# CH32L_VxxCx_Touch_Kit.net
KiCad netlist of a schematic drawn in Altium Designer
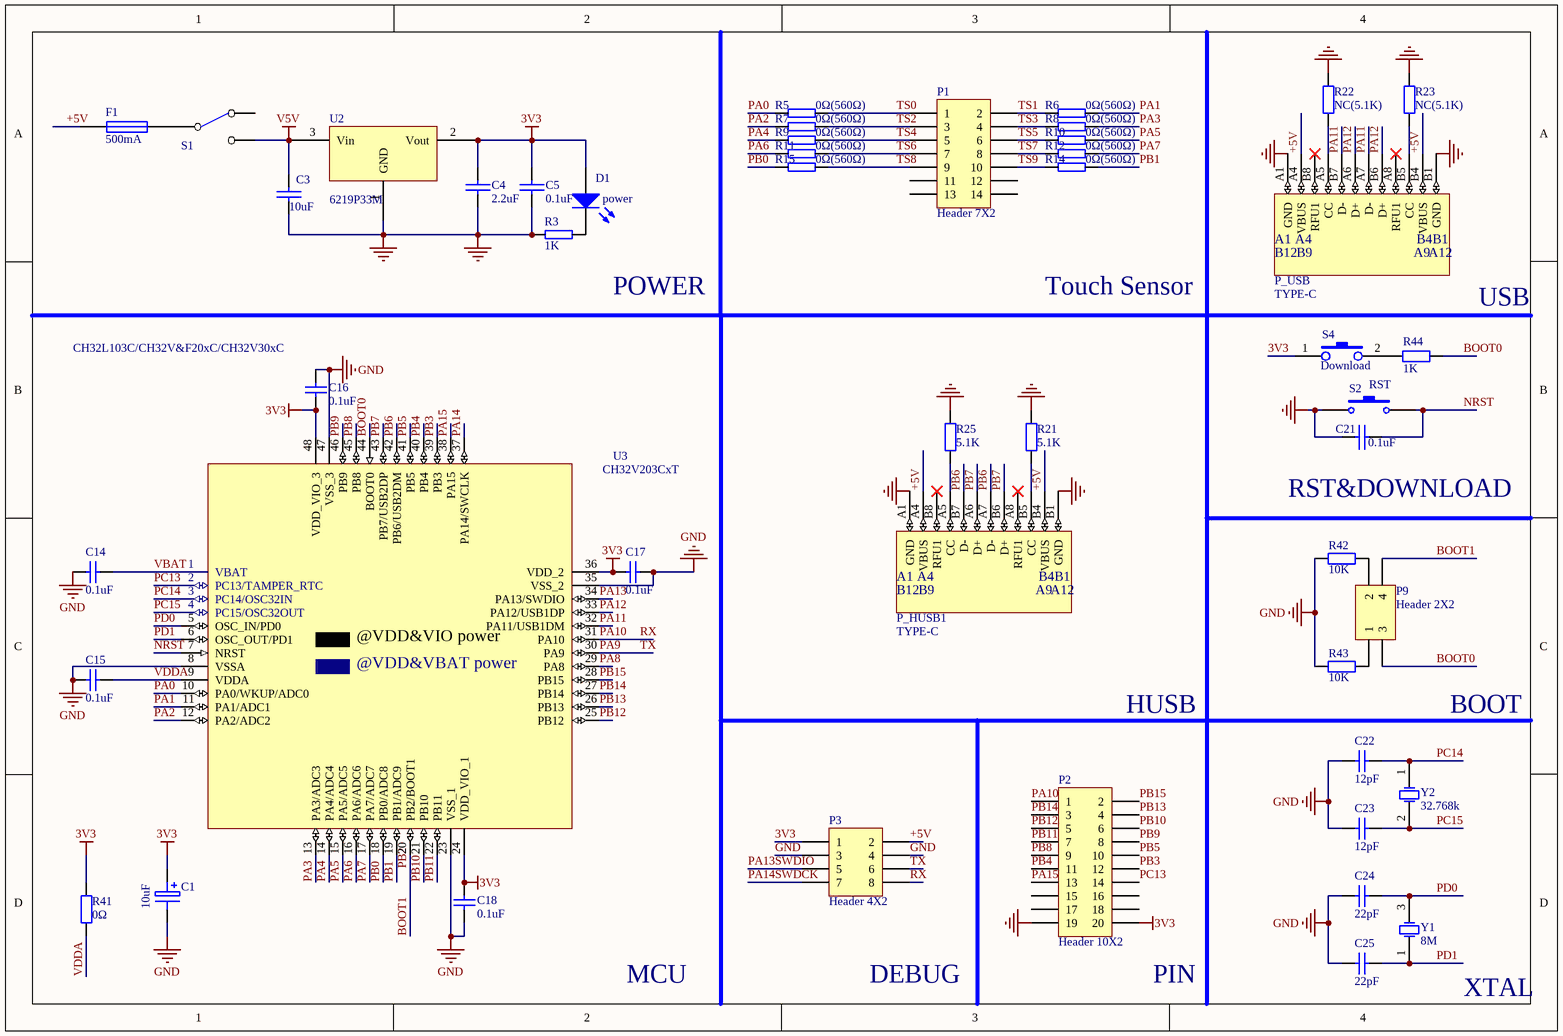
[diagram p0: CH32L&VxxCx_Touch_Kit.SchDoc]

(export (version "E")
  (design (tool "Eeschema 10.0.6"))
  (components
    (comp (ref "C1") (value "10uF") (footprint "CASE-A_3216") (libsource (lib "电阻电容") (part "T-A/4.7uF/16V")))
    (comp (ref "C3")
      (value "10uF")
      (footprint "0603_C")
      (description "Capacitor")
      (libsource (lib "*") (part "CAP"))
    )
    (comp (ref "C4")
      (value "2.2uF")
      (footprint "0402_C")
      (description "Capacitor")
      (libsource (lib "*") (part "CAP"))
    )
    (comp (ref "C5")
      (value "0.1uF")
      (footprint "0402_C")
      (description "Capacitor")
      (libsource (lib "*") (part "CAP"))
    )
    (comp (ref "C14")
      (value "0.1uF")
      (footprint "0402_C")
      (description "Capacitor")
      (fields (field (name "PUBLISHER") "Altium Limited"))
      (libsource (lib "Miscellaneous Devices") (part "Cap"))
    )
    (comp (ref "C15")
      (value "0.1uF")
      (footprint "0402_C")
      (description "Capacitor")
      (fields (field (name "PUBLISHER") "Altium Limited"))
      (libsource (lib "Miscellaneous Devices") (part "Cap"))
    )
    (comp (ref "C16")
      (value "0.1uF")
      (footprint "0402_C")
      (description "Capacitor")
      (fields (field (name "PUBLISHER") "Altium Limited"))
      (libsource (lib "Miscellaneous Devices") (part "Cap"))
    )
    (comp (ref "C17")
      (value "0.1uF")
      (footprint "0402_C")
      (description "Capacitor")
      (fields (field (name "PUBLISHER") "Altium Limited"))
      (libsource (lib "Miscellaneous Devices") (part "Cap"))
    )
    (comp (ref "C18")
      (value "0.1uF")
      (footprint "0402_C")
      (description "Capacitor")
      (fields (field (name "PUBLISHER") "Altium Limited"))
      (libsource (lib "Miscellaneous Devices") (part "Cap"))
    )
    (comp (ref "C21")
      (value "0.1uF")
      (footprint "0402_C")
      (description "Capacitor")
      (libsource (lib "") (part "CAP_1"))
    )
    (comp (ref "C22")
      (value "12pF")
      (footprint "0402_C")
      (description "Capacitor")
      (fields (field (name "PUBLISHER") "Altium Limited"))
      (libsource (lib "Miscellaneous Devices") (part "Cap"))
    )
    (comp (ref "C23")
      (value "12pF")
      (footprint "0402_C")
      (description "Capacitor")
      (fields (field (name "PUBLISHER") "Altium Limited"))
      (libsource (lib "Miscellaneous Devices") (part "Cap"))
    )
    (comp (ref "C24")
      (value "22pF")
      (footprint "0402_C")
      (description "Capacitor")
      (fields (field (name "PUBLISHER") "Altium Limited"))
      (libsource (lib "Miscellaneous Devices") (part "Cap"))
    )
    (comp (ref "C25")
      (value "22pF")
      (footprint "0402_C")
      (description "Capacitor")
      (fields (field (name "PUBLISHER") "Altium Limited"))
      (libsource (lib "Miscellaneous Devices") (part "Cap"))
    )
    (comp (ref "D1")
      (value "power")
      (footprint "0603+")
      (description "Typical INFRARED GaAs LED")
      (fields (field (name "PUBLISHER") "Altium Limited"))
      (libsource (lib "*") (part "LED0"))
    )
    (comp (ref "F1")
      (value "500mA")
      (footprint "0603")
      (description "Fuse")
      (libsource (lib "wch_sch_others") (part "FUSE1"))
    )
    (comp (ref "P1")
      (value "Header 7X2")
      (footprint "HDR-TH_14P-P2.54-H-M-R2-C10-S2.54")
      (description "Header, 7-Pin, Dual row")
      (fields (field (name "PUBLISHER") "Altium Limited"))
      (libsource (lib "Miscellaneous Connectors") (part "Header 7X2"))
    )
    (comp (ref "P2")
      (value "Header 10X2")
      (footprint "HDR-TH_20P-P2.54-H-M-R2-C10-S2.54")
      (description "Header, 10-Pin, Dual row")
      (fields (field (name "PUBLISHER") "Altium Limited"))
      (libsource (lib "Miscellaneous Connectors") (part "Header 10X2"))
    )
    (comp (ref "P3")
      (value "Header 4X2")
      (footprint "IDC8-2.54mm")
      (description "Header, 4-Pin, Dual row")
      (fields (field (name "PUBLISHER") "Altium Limited"))
      (libsource (lib "Miscellaneous Connectors") (part "Header 4X2"))
    )
    (comp (ref "P9")
      (value "Header 2X2")
      (footprint "IDC4-2.54mm")
      (description "Header, 2-Pin, Dual row")
      (fields (field (name "PUBLISHER") "Altium Limited"))
      (libsource (lib "Miscellaneous Connectors") (part "Header 2X2"))
    )
    (comp (ref "P_HUSB1")
      (value "TYPE-C")
      (footprint "TYPE-C-Receptacle-2.0")
      (libsource (lib "*") (part "TYPE-C1"))
    )
    (comp (ref "P_USB")
      (value "TYPE-C")
      (footprint "TYPE-C-Receptacle-2.0")
      (libsource (lib "*") (part "TYPE-C1"))
    )
    (comp (ref "R3") (value "1K") (footprint "0402") (libsource (lib "wch_sch_others") (part "RES")))
    (comp (ref "R5") (value "0Ω(560Ω)") (footprint "0402") (libsource (lib "wch_sch_others") (part "RES")))
    (comp (ref "R6") (value "0Ω(560Ω)") (footprint "0402") (libsource (lib "wch_sch_others") (part "RES")))
    (comp (ref "R7") (value "0Ω(560Ω)") (footprint "0402") (libsource (lib "wch_sch_others") (part "RES")))
    (comp (ref "R8") (value "0Ω(560Ω)") (footprint "0402") (libsource (lib "wch_sch_others") (part "RES")))
    (comp (ref "R9") (value "0Ω(560Ω)") (footprint "0402") (libsource (lib "wch_sch_others") (part "RES")))
    (comp (ref "R10") (value "0Ω(560Ω)") (footprint "0402") (libsource (lib "wch_sch_others") (part "RES")))
    (comp (ref "R11") (value "0Ω(560Ω)") (footprint "0402") (libsource (lib "wch_sch_others") (part "RES")))
    (comp (ref "R12") (value "0Ω(560Ω)") (footprint "0402") (libsource (lib "wch_sch_others") (part "RES")))
    (comp (ref "R14") (value "0Ω(560Ω)") (footprint "0402") (libsource (lib "wch_sch_others") (part "RES")))
    (comp (ref "R15") (value "0Ω(560Ω)") (footprint "0402") (libsource (lib "wch_sch_others") (part "RES")))
    (comp (ref "R21")
      (value "5.1K")
      (footprint "0402")
      (description "Resistor")
      (libsource (lib "Miscellaneous Devices") (part "Res2"))
    )
    (comp (ref "R22")
      (value "NC(5.1K)")
      (footprint "0402")
      (description "Resistor")
      (libsource (lib "Miscellaneous Devices") (part "Res2"))
    )
    (comp (ref "R23")
      (value "NC(5.1K)")
      (footprint "0402")
      (description "Resistor")
      (libsource (lib "Miscellaneous Devices") (part "Res2"))
    )
    (comp (ref "R25")
      (value "5.1K")
      (footprint "0402")
      (description "Resistor")
      (libsource (lib "Miscellaneous Devices") (part "Res2"))
    )
    (comp (ref "R41")
      (value "0Ω")
      (footprint "0402")
      (description "Resistor")
      (fields (field (name "PUBLISHER") "Altium Limited"))
      (libsource (lib "") (part "Res2_2"))
    )
    (comp (ref "R42")
      (value "10K")
      (footprint "0402")
      (description "Resistor")
      (fields (field (name "PUBLISHER") "Altium Limited"))
      (libsource (lib "") (part "Res2_1"))
    )
    (comp (ref "R43")
      (value "10K")
      (footprint "0402")
      (description "Resistor")
      (fields (field (name "PUBLISHER") "Altium Limited"))
      (libsource (lib "") (part "Res2_1"))
    )
    (comp (ref "R44")
      (value "1K")
      (footprint "0402")
      (description "Resistor")
      (fields (field (name "PUBLISHER") "Altium Limited"))
      (libsource (lib "") (part "Res2_1"))
    )
    (comp (ref "S1") (value "SW SPDT") (footprint "SW1") (libsource (lib "*") (part "SW SPDT")))
    (comp (ref "S2")
      (value "RST")
      (footprint "SMD_6.1x3.65x2.5mm-KEY")
      (description "Switch")
      (fields (field (name "PUBLISHER") "Altium Limited"))
      (libsource (lib "*") (part "SW-PB"))
    )
    (comp (ref "S4")
      (value "Download")
      (footprint "SMD_6.1x3.65x2.5mm-KEY")
      (libsource (lib "wch_sch_others") (part "KEY1"))
    )
    (comp (ref "U2")
      (value "6219P33M")
      (footprint "SOT-23")
      (libsource (lib "wch_sch_others") (part "6219P33M"))
    )
    (comp (ref "U3")
      (value "CH32V203CxT")
      (footprint "LQFP48")
      (description "RISC-V LMD-MCU, 144MHz, 2*USB FS, CAN")
      (libsource (lib "CHXXX") (part "CH32V203CxT"))
    )
    (comp (ref "Y1")
      (value "8M")
      (footprint "XT3225")
      (description "Crystal Oscillator")
      (fields (field (name "PUBLISHER") "Altium Limited"))
      (libsource (lib "Miscellaneous Devices") (part "XTAL"))
    )
    (comp (ref "Y2")
      (value "32.768k")
      (footprint "FC-135")
      (description "Crystal Oscillator")
      (fields (field (name "PUBLISHER") "Altium Limited"))
      (libsource (lib "") (part "XTAL_1"))
    )
  )
  (nets
    (net (code "1") (name "/+5V") (class "Default")
      (node (ref "F1") (pin "1") (pinfunction "1_1") (pintype "passive"))
      (node (ref "P3") (pin "2") (pinfunction "2_2") (pintype "passive"))
      (node (ref "P_HUSB1") (pin "A4") (pinfunction "VBUS_A4") (pintype "bidirectional"))
      (node (ref "P_HUSB1") (pin "B4") (pinfunction "VBUS_B4") (pintype "bidirectional"))
      (node (ref "P_USB") (pin "A4") (pinfunction "VBUS_A4") (pintype "bidirectional"))
      (node (ref "P_USB") (pin "B4") (pinfunction "VBUS_B4") (pintype "bidirectional"))
    )
    (net (code "2") (name "/BOOT0") (class "Default")
      (node (ref "P9") (pin "3") (pinfunction "3_3") (pintype "passive"))
      (node (ref "R44") (pin "1") (pinfunction "1_1") (pintype "passive"))
      (node (ref "U3") (pin "44") (pinfunction "BOOT0_44") (pintype "input"))
    )
    (net (code "3") (name "/BOOT1") (class "Default")
      (node (ref "P9") (pin "4") (pinfunction "4_4") (pintype "passive"))
      (node (ref "U3") (pin "20") (pinfunction "PB2/BOOT1_20") (pintype "bidirectional"))
    )
    (net (code "4") (name "/NRST") (class "Default")
      (node (ref "C21") (pin "2") (pinfunction "2_2") (pintype "passive"))
      (node (ref "S2") (pin "2") (pinfunction "2_2") (pintype "passive"))
      (node (ref "U3") (pin "7") (pinfunction "NRST_7") (pintype "input"))
    )
    (net (code "5") (name "/PA0") (class "Default")
      (node (ref "R5") (pin "1") (pintype "passive"))
      (node (ref "U3") (pin "10") (pinfunction "PA0/WKUP/ADC0_10") (pintype "bidirectional"))
    )
    (net (code "6") (name "/PA1") (class "Default")
      (node (ref "R6") (pin "2") (pintype "passive"))
      (node (ref "U3") (pin "11") (pinfunction "PA1/ADC1_11") (pintype "bidirectional"))
    )
    (net (code "7") (name "/PA2") (class "Default")
      (node (ref "R7") (pin "1") (pintype "passive"))
      (node (ref "U3") (pin "12") (pinfunction "PA2/ADC2_12") (pintype "bidirectional"))
    )
    (net (code "8") (name "/PA3") (class "Default")
      (node (ref "R8") (pin "2") (pintype "passive"))
      (node (ref "U3") (pin "13") (pinfunction "PA3/ADC3_13") (pintype "bidirectional"))
    )
    (net (code "9") (name "/PA4") (class "Default")
      (node (ref "R9") (pin "1") (pintype "passive"))
      (node (ref "U3") (pin "14") (pinfunction "PA4/ADC4_14") (pintype "bidirectional"))
    )
    (net (code "10") (name "/PA5") (class "Default")
      (node (ref "R10") (pin "2") (pintype "passive"))
      (node (ref "U3") (pin "15") (pinfunction "PA5/ADC5_15") (pintype "bidirectional"))
    )
    (net (code "11") (name "/PA6") (class "Default")
      (node (ref "R11") (pin "1") (pintype "passive"))
      (node (ref "U3") (pin "16") (pinfunction "PA6/ADC6_16") (pintype "bidirectional"))
    )
    (net (code "12") (name "/PA7") (class "Default")
      (node (ref "R12") (pin "2") (pintype "passive"))
      (node (ref "U3") (pin "17") (pinfunction "PA7/ADC7_17") (pintype "bidirectional"))
    )
    (net (code "13") (name "/PA8") (class "Default")
      (node (ref "U3") (pin "29") (pinfunction "PA8_29") (pintype "bidirectional"))
    )
    (net (code "14") (name "/PA9") (class "Default")
      (node (ref "P3") (pin "6") (pinfunction "6_6") (pintype "passive"))
      (node (ref "U3") (pin "30") (pinfunction "PA9_30") (pintype "bidirectional"))
    )
    (net (code "15") (name "/PA10") (class "Default")
      (node (ref "P2") (pin "1") (pinfunction "1_1") (pintype "passive"))
      (node (ref "P3") (pin "8") (pinfunction "8_8") (pintype "passive"))
      (node (ref "U3") (pin "31") (pinfunction "PA10_31") (pintype "bidirectional"))
    )
    (net (code "16") (name "/PA11") (class "Default")
      (node (ref "P_USB") (pin "A7") (pinfunction "D-_A7") (pintype "bidirectional"))
      (node (ref "P_USB") (pin "B7") (pinfunction "D-_B7") (pintype "bidirectional"))
      (node (ref "U3") (pin "32") (pinfunction "PA11/USB1DM_32") (pintype "bidirectional"))
    )
    (net (code "17") (name "/PA12") (class "Default")
      (node (ref "P_USB") (pin "A6") (pinfunction "D+_A6") (pintype "bidirectional"))
      (node (ref "P_USB") (pin "B6") (pinfunction "D+_B6") (pintype "bidirectional"))
      (node (ref "U3") (pin "33") (pinfunction "PA12/USB1DP_33") (pintype "bidirectional"))
    )
    (net (code "18") (name "/PA13") (class "Default")
      (node (ref "P3") (pin "5") (pinfunction "5_5") (pintype "passive"))
      (node (ref "U3") (pin "34") (pinfunction "PA13/SWDIO_34") (pintype "bidirectional"))
    )
    (net (code "19") (name "/PA14") (class "Default")
      (node (ref "P3") (pin "7") (pinfunction "7_7") (pintype "passive"))
      (node (ref "U3") (pin "37") (pinfunction "PA14/SWCLK_37") (pintype "bidirectional"))
    )
    (net (code "20") (name "/PA15") (class "Default")
      (node (ref "P2") (pin "13") (pinfunction "13_13") (pintype "passive"))
      (node (ref "U3") (pin "38") (pinfunction "PA15_38") (pintype "bidirectional"))
    )
    (net (code "21") (name "/PB0") (class "Default")
      (node (ref "R15") (pin "1") (pintype "passive"))
      (node (ref "U3") (pin "18") (pinfunction "PB0/ADC8_18") (pintype "bidirectional"))
    )
    (net (code "22") (name "/PB1") (class "Default")
      (node (ref "R14") (pin "2") (pintype "passive"))
      (node (ref "U3") (pin "19") (pinfunction "PB1/ADC9_19") (pintype "bidirectional"))
    )
    (net (code "23") (name "/PB3") (class "Default")
      (node (ref "P2") (pin "12") (pinfunction "12_12") (pintype "passive"))
      (node (ref "U3") (pin "39") (pinfunction "PB3_39") (pintype "bidirectional"))
    )
    (net (code "24") (name "/PB4") (class "Default")
      (node (ref "P2") (pin "11") (pinfunction "11_11") (pintype "passive"))
      (node (ref "U3") (pin "40") (pinfunction "PB4_40") (pintype "bidirectional"))
    )
    (net (code "25") (name "/PB5") (class "Default")
      (node (ref "P2") (pin "10") (pinfunction "10_10") (pintype "passive"))
      (node (ref "U3") (pin "41") (pinfunction "PB5_41") (pintype "bidirectional"))
    )
    (net (code "26") (name "/PB6") (class "Default")
      (node (ref "P_HUSB1") (pin "A7") (pinfunction "D-_A7") (pintype "bidirectional"))
      (node (ref "P_HUSB1") (pin "B7") (pinfunction "D-_B7") (pintype "bidirectional"))
      (node (ref "U3") (pin "42") (pinfunction "PB6/USB2DM_42") (pintype "bidirectional"))
    )
    (net (code "27") (name "/PB7") (class "Default")
      (node (ref "P_HUSB1") (pin "A6") (pinfunction "D+_A6") (pintype "bidirectional"))
      (node (ref "P_HUSB1") (pin "B6") (pinfunction "D+_B6") (pintype "bidirectional"))
      (node (ref "U3") (pin "43") (pinfunction "PB7/USB2DP_43") (pintype "bidirectional"))
    )
    (net (code "28") (name "/PB8") (class "Default")
      (node (ref "P2") (pin "9") (pinfunction "9_9") (pintype "passive"))
      (node (ref "U3") (pin "45") (pinfunction "PB8_45") (pintype "bidirectional"))
    )
    (net (code "29") (name "/PB9") (class "Default")
      (node (ref "P2") (pin "8") (pinfunction "8_8") (pintype "passive"))
      (node (ref "U3") (pin "46") (pinfunction "PB9_46") (pintype "bidirectional"))
    )
    (net (code "30") (name "/PB10") (class "Default")
      (node (ref "P2") (pin "6") (pinfunction "6_6") (pintype "passive"))
      (node (ref "U3") (pin "21") (pinfunction "PB10_21") (pintype "bidirectional"))
    )
    (net (code "31") (name "/PB11") (class "Default")
      (node (ref "P2") (pin "7") (pinfunction "7_7") (pintype "passive"))
      (node (ref "U3") (pin "22") (pinfunction "PB11_22") (pintype "bidirectional"))
    )
    (net (code "32") (name "/PB12") (class "Default")
      (node (ref "P2") (pin "5") (pinfunction "5_5") (pintype "passive"))
      (node (ref "U3") (pin "25") (pinfunction "PB12_25") (pintype "bidirectional"))
    )
    (net (code "33") (name "/PB13") (class "Default")
      (node (ref "P2") (pin "4") (pinfunction "4_4") (pintype "passive"))
      (node (ref "U3") (pin "26") (pinfunction "PB13_26") (pintype "bidirectional"))
    )
    (net (code "34") (name "/PB14") (class "Default")
      (node (ref "P2") (pin "3") (pinfunction "3_3") (pintype "passive"))
      (node (ref "U3") (pin "27") (pinfunction "PB14_27") (pintype "bidirectional"))
    )
    (net (code "35") (name "/PB15") (class "Default")
      (node (ref "P2") (pin "2") (pinfunction "2_2") (pintype "passive"))
      (node (ref "U3") (pin "28") (pinfunction "PB15_28") (pintype "bidirectional"))
    )
    (net (code "36") (name "/PC13") (class "Default")
      (node (ref "P2") (pin "14") (pinfunction "14_14") (pintype "passive"))
      (node (ref "U3") (pin "2") (pinfunction "PC13/TAMPER_RTC_2") (pintype "bidirectional"))
    )
    (net (code "37") (name "/PC14") (class "Default")
      (node (ref "C22") (pin "1") (pinfunction "1_1") (pintype "passive"))
      (node (ref "U3") (pin "3") (pinfunction "PC14/OSC32IN_3") (pintype "bidirectional"))
      (node (ref "Y2") (pin "1") (pinfunction "OSC1_1") (pintype "passive"))
    )
    (net (code "38") (name "/PC15") (class "Default")
      (node (ref "C23") (pin "1") (pinfunction "1_1") (pintype "passive"))
      (node (ref "U3") (pin "4") (pinfunction "PC15/OSC32OUT_4") (pintype "bidirectional"))
      (node (ref "Y2") (pin "2") (pinfunction "OSC2_2") (pintype "passive"))
    )
    (net (code "39") (name "/PD0") (class "Default")
      (node (ref "C24") (pin "2") (pinfunction "2_2") (pintype "passive"))
      (node (ref "U3") (pin "5") (pinfunction "OSC_IN/PD0_5") (pintype "bidirectional"))
      (node (ref "Y1") (pin "3") (pinfunction "OSC2_3") (pintype "passive"))
    )
    (net (code "40") (name "/PD1") (class "Default")
      (node (ref "C25") (pin "2") (pinfunction "2_2") (pintype "passive"))
      (node (ref "U3") (pin "6") (pinfunction "OSC_OUT/PD1_6") (pintype "bidirectional"))
      (node (ref "Y1") (pin "1") (pinfunction "OSC1_1") (pintype "passive"))
    )
    (net (code "41") (name "/TS0") (class "Default")
      (node (ref "P1") (pin "1") (pinfunction "1_1") (pintype "passive"))
      (node (ref "R5") (pin "2") (pintype "passive"))
    )
    (net (code "42") (name "/TS1") (class "Default")
      (node (ref "P1") (pin "2") (pinfunction "2_2") (pintype "passive"))
      (node (ref "R6") (pin "1") (pintype "passive"))
    )
    (net (code "43") (name "/TS2") (class "Default")
      (node (ref "P1") (pin "3") (pinfunction "3_3") (pintype "passive"))
      (node (ref "R7") (pin "2") (pintype "passive"))
    )
    (net (code "44") (name "/TS3") (class "Default")
      (node (ref "P1") (pin "4") (pinfunction "4_4") (pintype "passive"))
      (node (ref "R8") (pin "1") (pintype "passive"))
    )
    (net (code "45") (name "/TS4") (class "Default")
      (node (ref "P1") (pin "5") (pinfunction "5_5") (pintype "passive"))
      (node (ref "R9") (pin "2") (pintype "passive"))
    )
    (net (code "46") (name "/TS5") (class "Default")
      (node (ref "P1") (pin "6") (pinfunction "6_6") (pintype "passive"))
      (node (ref "R10") (pin "1") (pintype "passive"))
    )
    (net (code "47") (name "/TS6") (class "Default")
      (node (ref "P1") (pin "7") (pinfunction "7_7") (pintype "passive"))
      (node (ref "R11") (pin "2") (pintype "passive"))
    )
    (net (code "48") (name "/TS7") (class "Default")
      (node (ref "P1") (pin "8") (pinfunction "8_8") (pintype "passive"))
      (node (ref "R12") (pin "1") (pintype "passive"))
    )
    (net (code "49") (name "/TS8") (class "Default")
      (node (ref "P1") (pin "9") (pinfunction "9_9") (pintype "passive"))
      (node (ref "R15") (pin "2") (pintype "passive"))
    )
    (net (code "50") (name "/TS9") (class "Default")
      (node (ref "P1") (pin "10") (pinfunction "10_10") (pintype "passive"))
      (node (ref "R14") (pin "1") (pintype "passive"))
    )
    (net (code "51") (name "/VBAT") (class "Default")
      (node (ref "C14") (pin "1") (pinfunction "1_1") (pintype "passive"))
      (node (ref "U3") (pin "1") (pinfunction "VBAT_1") (pintype "power_in"))
    )
    (net (code "52") (name "/VDDA") (class "Default")
      (node (ref "C15") (pin "1") (pinfunction "1_1") (pintype "passive"))
      (node (ref "R41") (pin "2") (pinfunction "2_2") (pintype "passive"))
      (node (ref "U3") (pin "9") (pinfunction "VDDA_9") (pintype "power_in"))
    )
    (net (code "53") (name "3V3") (class "Default")
      (node (ref "C1") (pin "1") (pinfunction "1_1") (pintype "passive"))
      (node (ref "C16") (pin "2") (pinfunction "2_2") (pintype "passive"))
      (node (ref "C17") (pin "2") (pinfunction "2_2") (pintype "passive"))
      (node (ref "C18") (pin "2") (pinfunction "2_2") (pintype "passive"))
      (node (ref "C4") (pin "1") (pinfunction "1_1") (pintype "passive"))
      (node (ref "C5") (pin "1") (pinfunction "1_1") (pintype "passive"))
      (node (ref "D1") (pin "1") (pinfunction "A_1") (pintype "passive"))
      (node (ref "P2") (pin "20") (pinfunction "20_20") (pintype "passive"))
      (node (ref "P3") (pin "1") (pinfunction "1_1") (pintype "passive"))
      (node (ref "R41") (pin "1") (pinfunction "1_1") (pintype "passive"))
      (node (ref "S4") (pin "1") (pinfunction "1_1") (pintype "passive"))
      (node (ref "U2") (pin "2") (pinfunction "Vout_2") (pintype "passive"))
      (node (ref "U3") (pin "24") (pinfunction "VDD_VIO_1_24") (pintype "power_in"))
      (node (ref "U3") (pin "36") (pinfunction "VDD_2_36") (pintype "power_in"))
      (node (ref "U3") (pin "48") (pinfunction "VDD_VIO_3_48") (pintype "power_in"))
    )
    (net (code "54") (name "GND") (class "Default")
      (node (ref "C1") (pin "2") (pinfunction "2_2") (pintype "passive"))
      (node (ref "C14") (pin "2") (pinfunction "2_2") (pintype "passive"))
      (node (ref "C15") (pin "2") (pinfunction "2_2") (pintype "passive"))
      (node (ref "C16") (pin "1") (pinfunction "1_1") (pintype "passive"))
      (node (ref "C17") (pin "1") (pinfunction "1_1") (pintype "passive"))
      (node (ref "C18") (pin "1") (pinfunction "1_1") (pintype "passive"))
      (node (ref "C21") (pin "1") (pinfunction "1_1") (pintype "passive"))
      (node (ref "C22") (pin "2") (pinfunction "2_2") (pintype "passive"))
      (node (ref "C23") (pin "2") (pinfunction "2_2") (pintype "passive"))
      (node (ref "C24") (pin "1") (pinfunction "1_1") (pintype "passive"))
      (node (ref "C25") (pin "1") (pinfunction "1_1") (pintype "passive"))
      (node (ref "C3") (pin "2") (pinfunction "2_2") (pintype "passive"))
      (node (ref "C4") (pin "2") (pinfunction "2_2") (pintype "passive"))
      (node (ref "C5") (pin "2") (pinfunction "2_2") (pintype "passive"))
      (node (ref "P2") (pin "19") (pinfunction "19_19") (pintype "passive"))
      (node (ref "P3") (pin "3") (pinfunction "3_3") (pintype "passive"))
      (node (ref "P3") (pin "4") (pinfunction "4_4") (pintype "passive"))
      (node (ref "P_HUSB1") (pin "A1") (pinfunction "GND_A1") (pintype "bidirectional"))
      (node (ref "P_HUSB1") (pin "B1") (pinfunction "GND_B1") (pintype "bidirectional"))
      (node (ref "P_USB") (pin "A1") (pinfunction "GND_A1") (pintype "bidirectional"))
      (node (ref "P_USB") (pin "B1") (pinfunction "GND_B1") (pintype "bidirectional"))
      (node (ref "R21") (pin "2") (pinfunction "2_2") (pintype "passive"))
      (node (ref "R22") (pin "2") (pinfunction "2_2") (pintype "passive"))
      (node (ref "R23") (pin "2") (pinfunction "2_2") (pintype "passive"))
      (node (ref "R25") (pin "2") (pinfunction "2_2") (pintype "passive"))
      (node (ref "R3") (pin "2") (pintype "passive"))
      (node (ref "R42") (pin "2") (pinfunction "2_2") (pintype "passive"))
      (node (ref "R43") (pin "2") (pinfunction "2_2") (pintype "passive"))
      (node (ref "S2") (pin "1") (pinfunction "1_1") (pintype "passive"))
      (node (ref "U2") (pin "1") (pinfunction "GND_1") (pintype "passive"))
      (node (ref "U3") (pin "23") (pinfunction "VSS_1_23") (pintype "power_in"))
      (node (ref "U3") (pin "35") (pinfunction "VSS_2_35") (pintype "power_in"))
      (node (ref "U3") (pin "47") (pinfunction "VSS_3_47") (pintype "power_in"))
      (node (ref "U3") (pin "8") (pinfunction "VSSA_8") (pintype "power_in"))
    )
    (net (code "55") (name "Net-(D1-K)") (class "Default")
      (node (ref "D1") (pin "2") (pinfunction "K_2") (pintype "passive"))
      (node (ref "R3") (pin "1") (pintype "passive"))
    )
    (net (code "56") (name "Net-(P9-Pad1)") (class "Default")
      (node (ref "P9") (pin "1") (pinfunction "1_1") (pintype "passive"))
      (node (ref "R43") (pin "1") (pinfunction "1_1") (pintype "passive"))
    )
    (net (code "57") (name "Net-(P9-Pad2)") (class "Default")
      (node (ref "P9") (pin "2") (pinfunction "2_2") (pintype "passive"))
      (node (ref "R42") (pin "1") (pinfunction "1_1") (pintype "passive"))
    )
    (net (code "58") (name "Net-(P_HUSB1-CC-PadA5)") (class "Default")
      (node (ref "P_HUSB1") (pin "A5") (pinfunction "CC_A5") (pintype "bidirectional"))
      (node (ref "R25") (pin "1") (pinfunction "1_1") (pintype "passive"))
    )
    (net (code "59") (name "Net-(P_HUSB1-CC-PadB5)") (class "Default")
      (node (ref "P_HUSB1") (pin "B5") (pinfunction "CC_B5") (pintype "bidirectional"))
      (node (ref "R21") (pin "1") (pinfunction "1_1") (pintype "passive"))
    )
    (net (code "60") (name "Net-(P_USB-CC-PadA5)") (class "Default")
      (node (ref "P_USB") (pin "A5") (pinfunction "CC_A5") (pintype "bidirectional"))
      (node (ref "R22") (pin "1") (pinfunction "1_1") (pintype "passive"))
    )
    (net (code "61") (name "Net-(P_USB-CC-PadB5)") (class "Default")
      (node (ref "P_USB") (pin "B5") (pinfunction "CC_B5") (pintype "bidirectional"))
      (node (ref "R23") (pin "1") (pinfunction "1_1") (pintype "passive"))
    )
    (net (code "62") (name "Net-(R44-Pad2)") (class "Default")
      (node (ref "R44") (pin "2") (pinfunction "2_2") (pintype "passive"))
      (node (ref "S4") (pin "2") (pinfunction "2_2") (pintype "passive"))
    )
    (net (code "63") (name "Net-(S1-COMMON)") (class "Default")
      (node (ref "F1") (pin "2") (pinfunction "2_2") (pintype "passive"))
      (node (ref "S1") (pin "1") (pinfunction "COMMON_1") (pintype "passive"))
    )
    (net (code "64") (name "V5V") (class "Default")
      (node (ref "C3") (pin "1") (pinfunction "1_1") (pintype "passive"))
      (node (ref "S1") (pin "2") (pinfunction "NC_2") (pintype "passive"))
      (node (ref "U2") (pin "3") (pinfunction "Vin_3") (pintype "passive"))
    )
    (net (code "65") (name "unconnected-(P1-Pad11)") (class "Default")
      (node (ref "P1") (pin "11") (pinfunction "11_11") (pintype "passive"))
    )
    (net (code "66") (name "unconnected-(P1-Pad12)") (class "Default")
      (node (ref "P1") (pin "12") (pinfunction "12_12") (pintype "passive"))
    )
    (net (code "67") (name "unconnected-(P1-Pad13)") (class "Default")
      (node (ref "P1") (pin "13") (pinfunction "13_13") (pintype "passive"))
    )
    (net (code "68") (name "unconnected-(P1-Pad14)") (class "Default")
      (node (ref "P1") (pin "14") (pinfunction "14_14") (pintype "passive"))
    )
    (net (code "69") (name "unconnected-(P2-Pad15)") (class "Default")
      (node (ref "P2") (pin "15") (pinfunction "15_15") (pintype "passive"))
    )
    (net (code "70") (name "unconnected-(P2-Pad16)") (class "Default")
      (node (ref "P2") (pin "16") (pinfunction "16_16") (pintype "passive"))
    )
    (net (code "71") (name "unconnected-(P2-Pad17)") (class "Default")
      (node (ref "P2") (pin "17") (pinfunction "17_17") (pintype "passive"))
    )
    (net (code "72") (name "unconnected-(P2-Pad18)") (class "Default")
      (node (ref "P2") (pin "18") (pinfunction "18_18") (pintype "passive"))
    )
    (net (code "73") (name "unconnected-(P_HUSB1-RFU1-PadA8)") (class "Default")
      (node (ref "P_HUSB1") (pin "A8") (pinfunction "RFU1_A8") (pintype "bidirectional+no_connect"))
    )
    (net (code "74") (name "unconnected-(P_HUSB1-RFU1-PadB8)") (class "Default")
      (node (ref "P_HUSB1") (pin "B8") (pinfunction "RFU1_B8") (pintype "bidirectional+no_connect"))
    )
    (net (code "75") (name "unconnected-(P_USB-RFU1-PadA8)") (class "Default")
      (node (ref "P_USB") (pin "A8") (pinfunction "RFU1_A8") (pintype "bidirectional+no_connect"))
    )
    (net (code "76") (name "unconnected-(P_USB-RFU1-PadB8)") (class "Default")
      (node (ref "P_USB") (pin "B8") (pinfunction "RFU1_B8") (pintype "bidirectional+no_connect"))
    )
    (net (code "77") (name "unconnected-(S1-NO-Pad3)") (class "Default")
      (node (ref "S1") (pin "3") (pinfunction "NO_3") (pintype "passive"))
    )
  )
)
